# 04_PCIe.net
KiCad netlist of a schematic drawn in Altium Designer
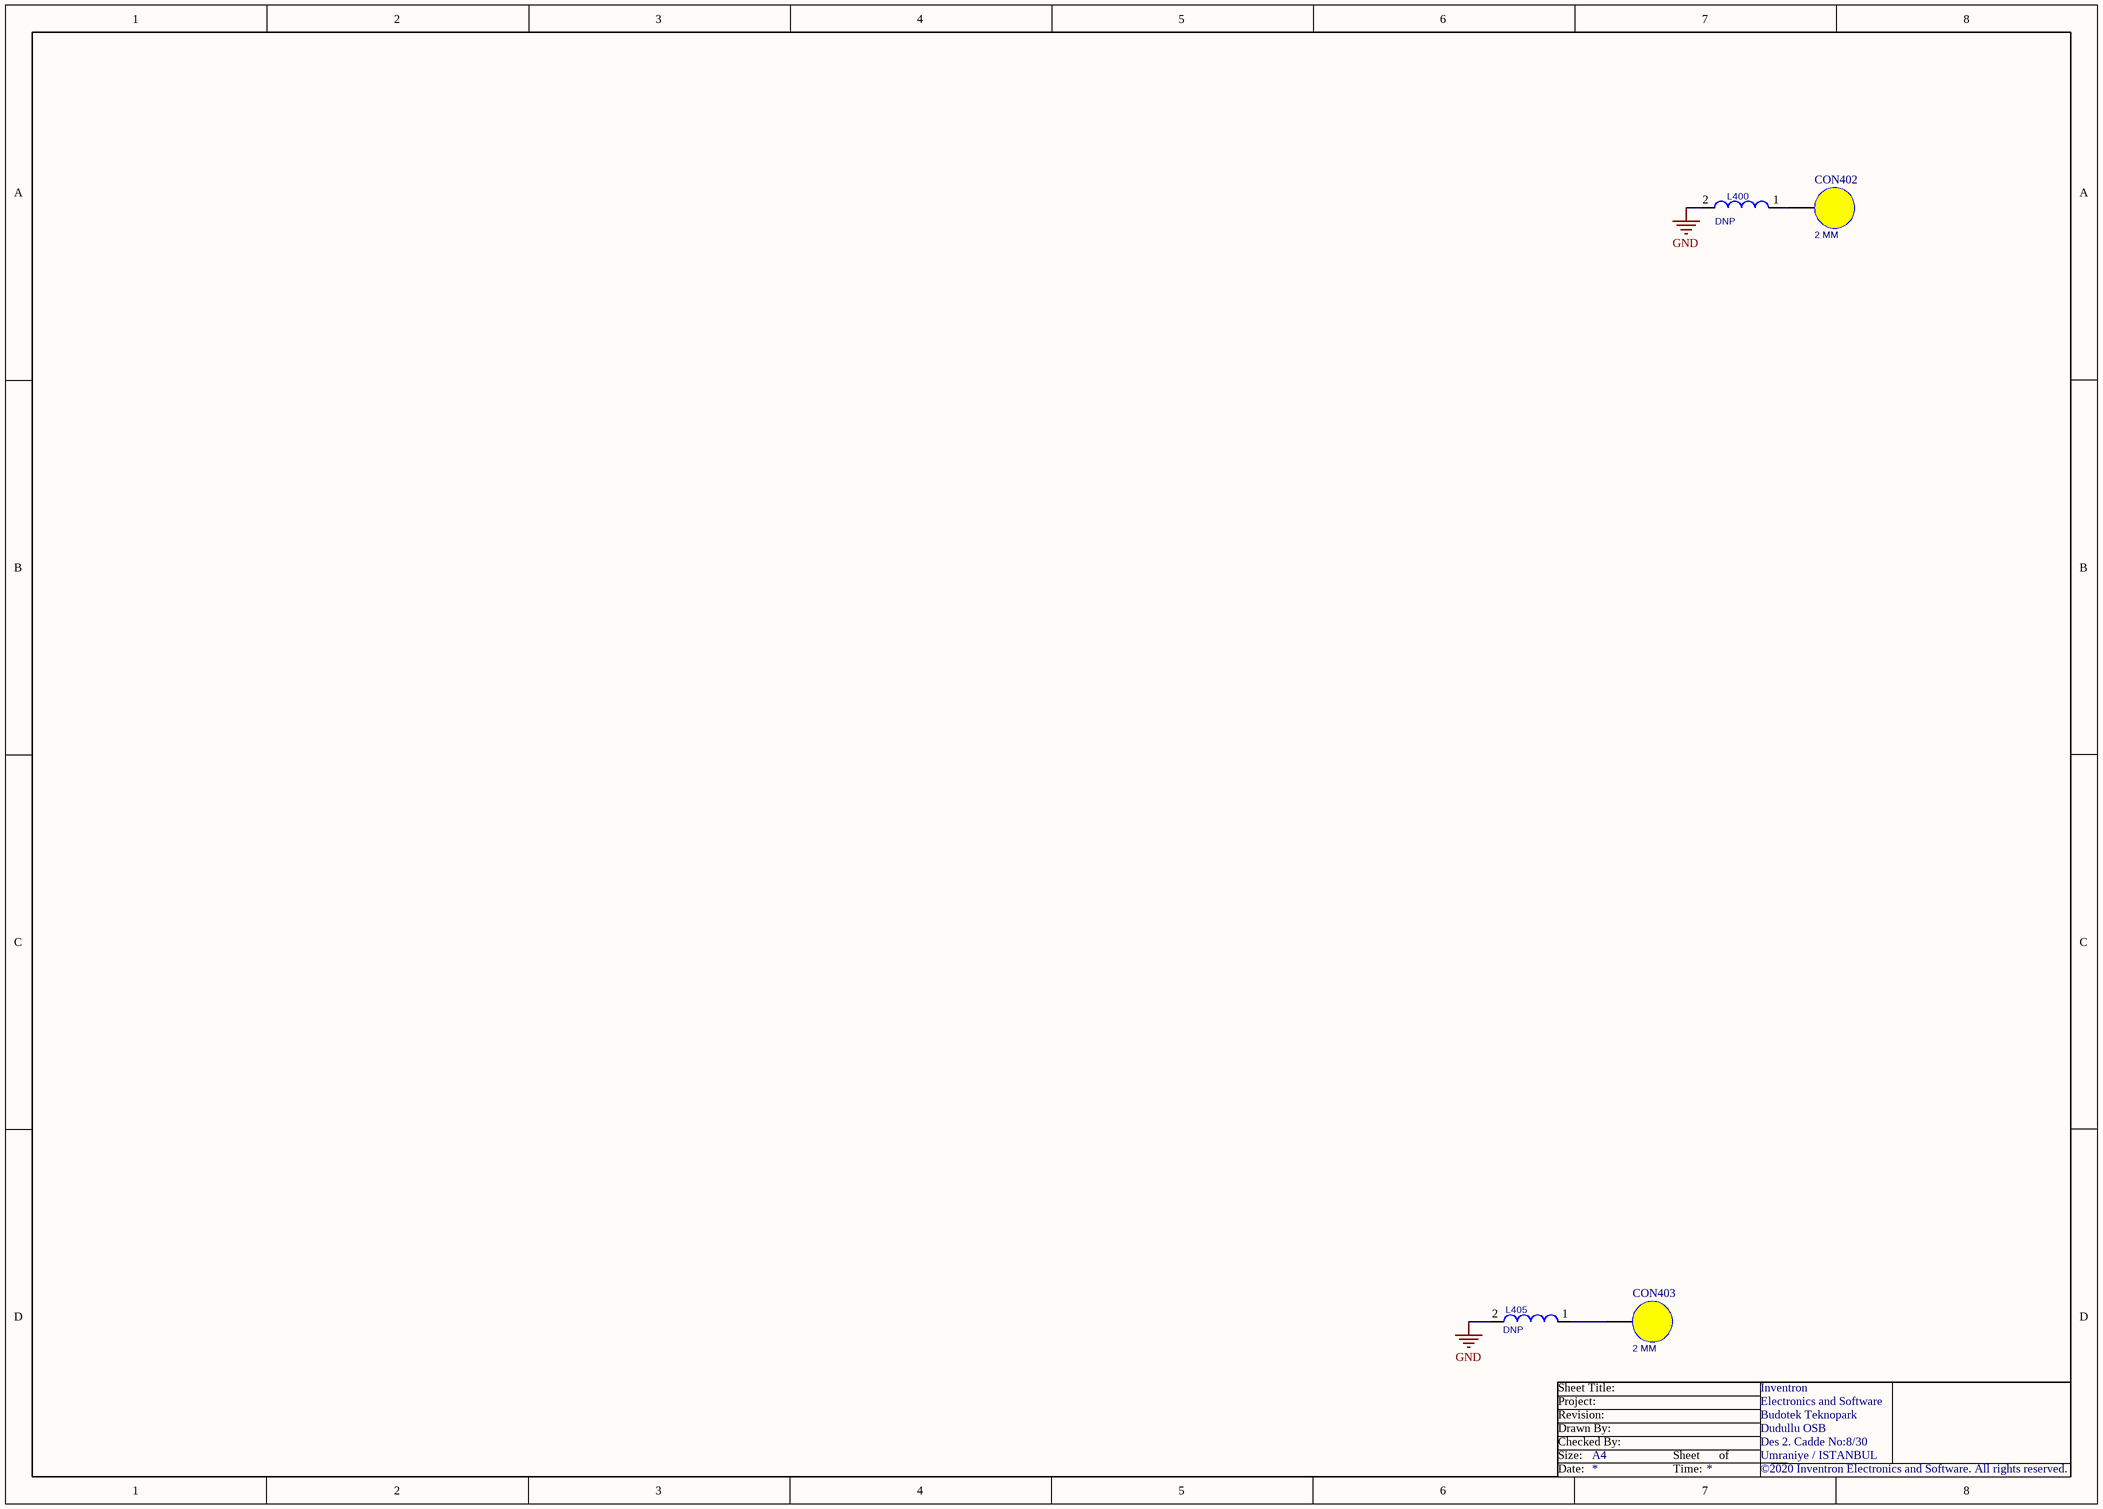
[diagram p0: 04 PCIe.SchDoc]

(export (version "E")
  (design (tool "Eeschema 10.0.6"))
  (components
    (comp (ref "CON402")
      (value "2 MM")
      (footprint "9774045243R")
      (description "Round Standoff Threaded M2x0.4 Steel 0.177\" (4.50mm)")
      (fields (field (name "CREATED BY") "EE") (field (name "CHECKED BY") "*"))
      (libsource (lib "ARETE_SCH") (part "CON-9774045243R"))
    )
    (comp (ref "CON403")
      (value "2 MM")
      (footprint "9774045243R")
      (description "Round Standoff Threaded M2x0.4 Steel 0.177\" (4.50mm)")
      (fields (field (name "CREATED BY") "EE") (field (name "CHECKED BY") "*"))
      (libsource (lib "ARETE_SCH") (part "CON-9774045243R"))
    )
    (comp (ref "L400")
      (value "FERRITE 0603")
      (footprint "0603_RES")
      (description "FERRITE BEAD 0603")
      (fields (field (name "ASSY_OPT") "DNP") (field (name "CHECKED BY") "*"))
      (libsource (lib "ARETE_L") (part "IND-FERRITE 0603"))
    )
    (comp (ref "L405")
      (value "FERRITE 0603")
      (footprint "0603_RES")
      (description "FERRITE BEAD 0603")
      (fields (field (name "ASSY_OPT") "DNP") (field (name "CHECKED BY") "*"))
      (libsource (lib "ARETE_L") (part "IND-FERRITE 0603"))
    )
  )
  (nets
    (net (code "1") (name "GND") (class "Default")
      (node (ref "L400") (pin "2") (pinfunction "2_2") (pintype "passive"))
      (node (ref "L405") (pin "2") (pinfunction "2_2") (pintype "passive"))
    )
    (net (code "2") (name "Net-(CON402-0)") (class "Default")
      (node (ref "CON402") (pin "1") (pinfunction "0_1") (pintype "passive"))
      (node (ref "L400") (pin "1") (pinfunction "1_1") (pintype "passive"))
    )
    (net (code "3") (name "Net-(CON403-0)") (class "Default")
      (node (ref "CON403") (pin "1") (pinfunction "0_1") (pintype "passive"))
      (node (ref "L405") (pin "1") (pinfunction "1_1") (pintype "passive"))
    )
  )
)
